# ProProject__STC8H_2024-07-14.net
KiCad netlist of a schematic drawn in EasyEDA Pro
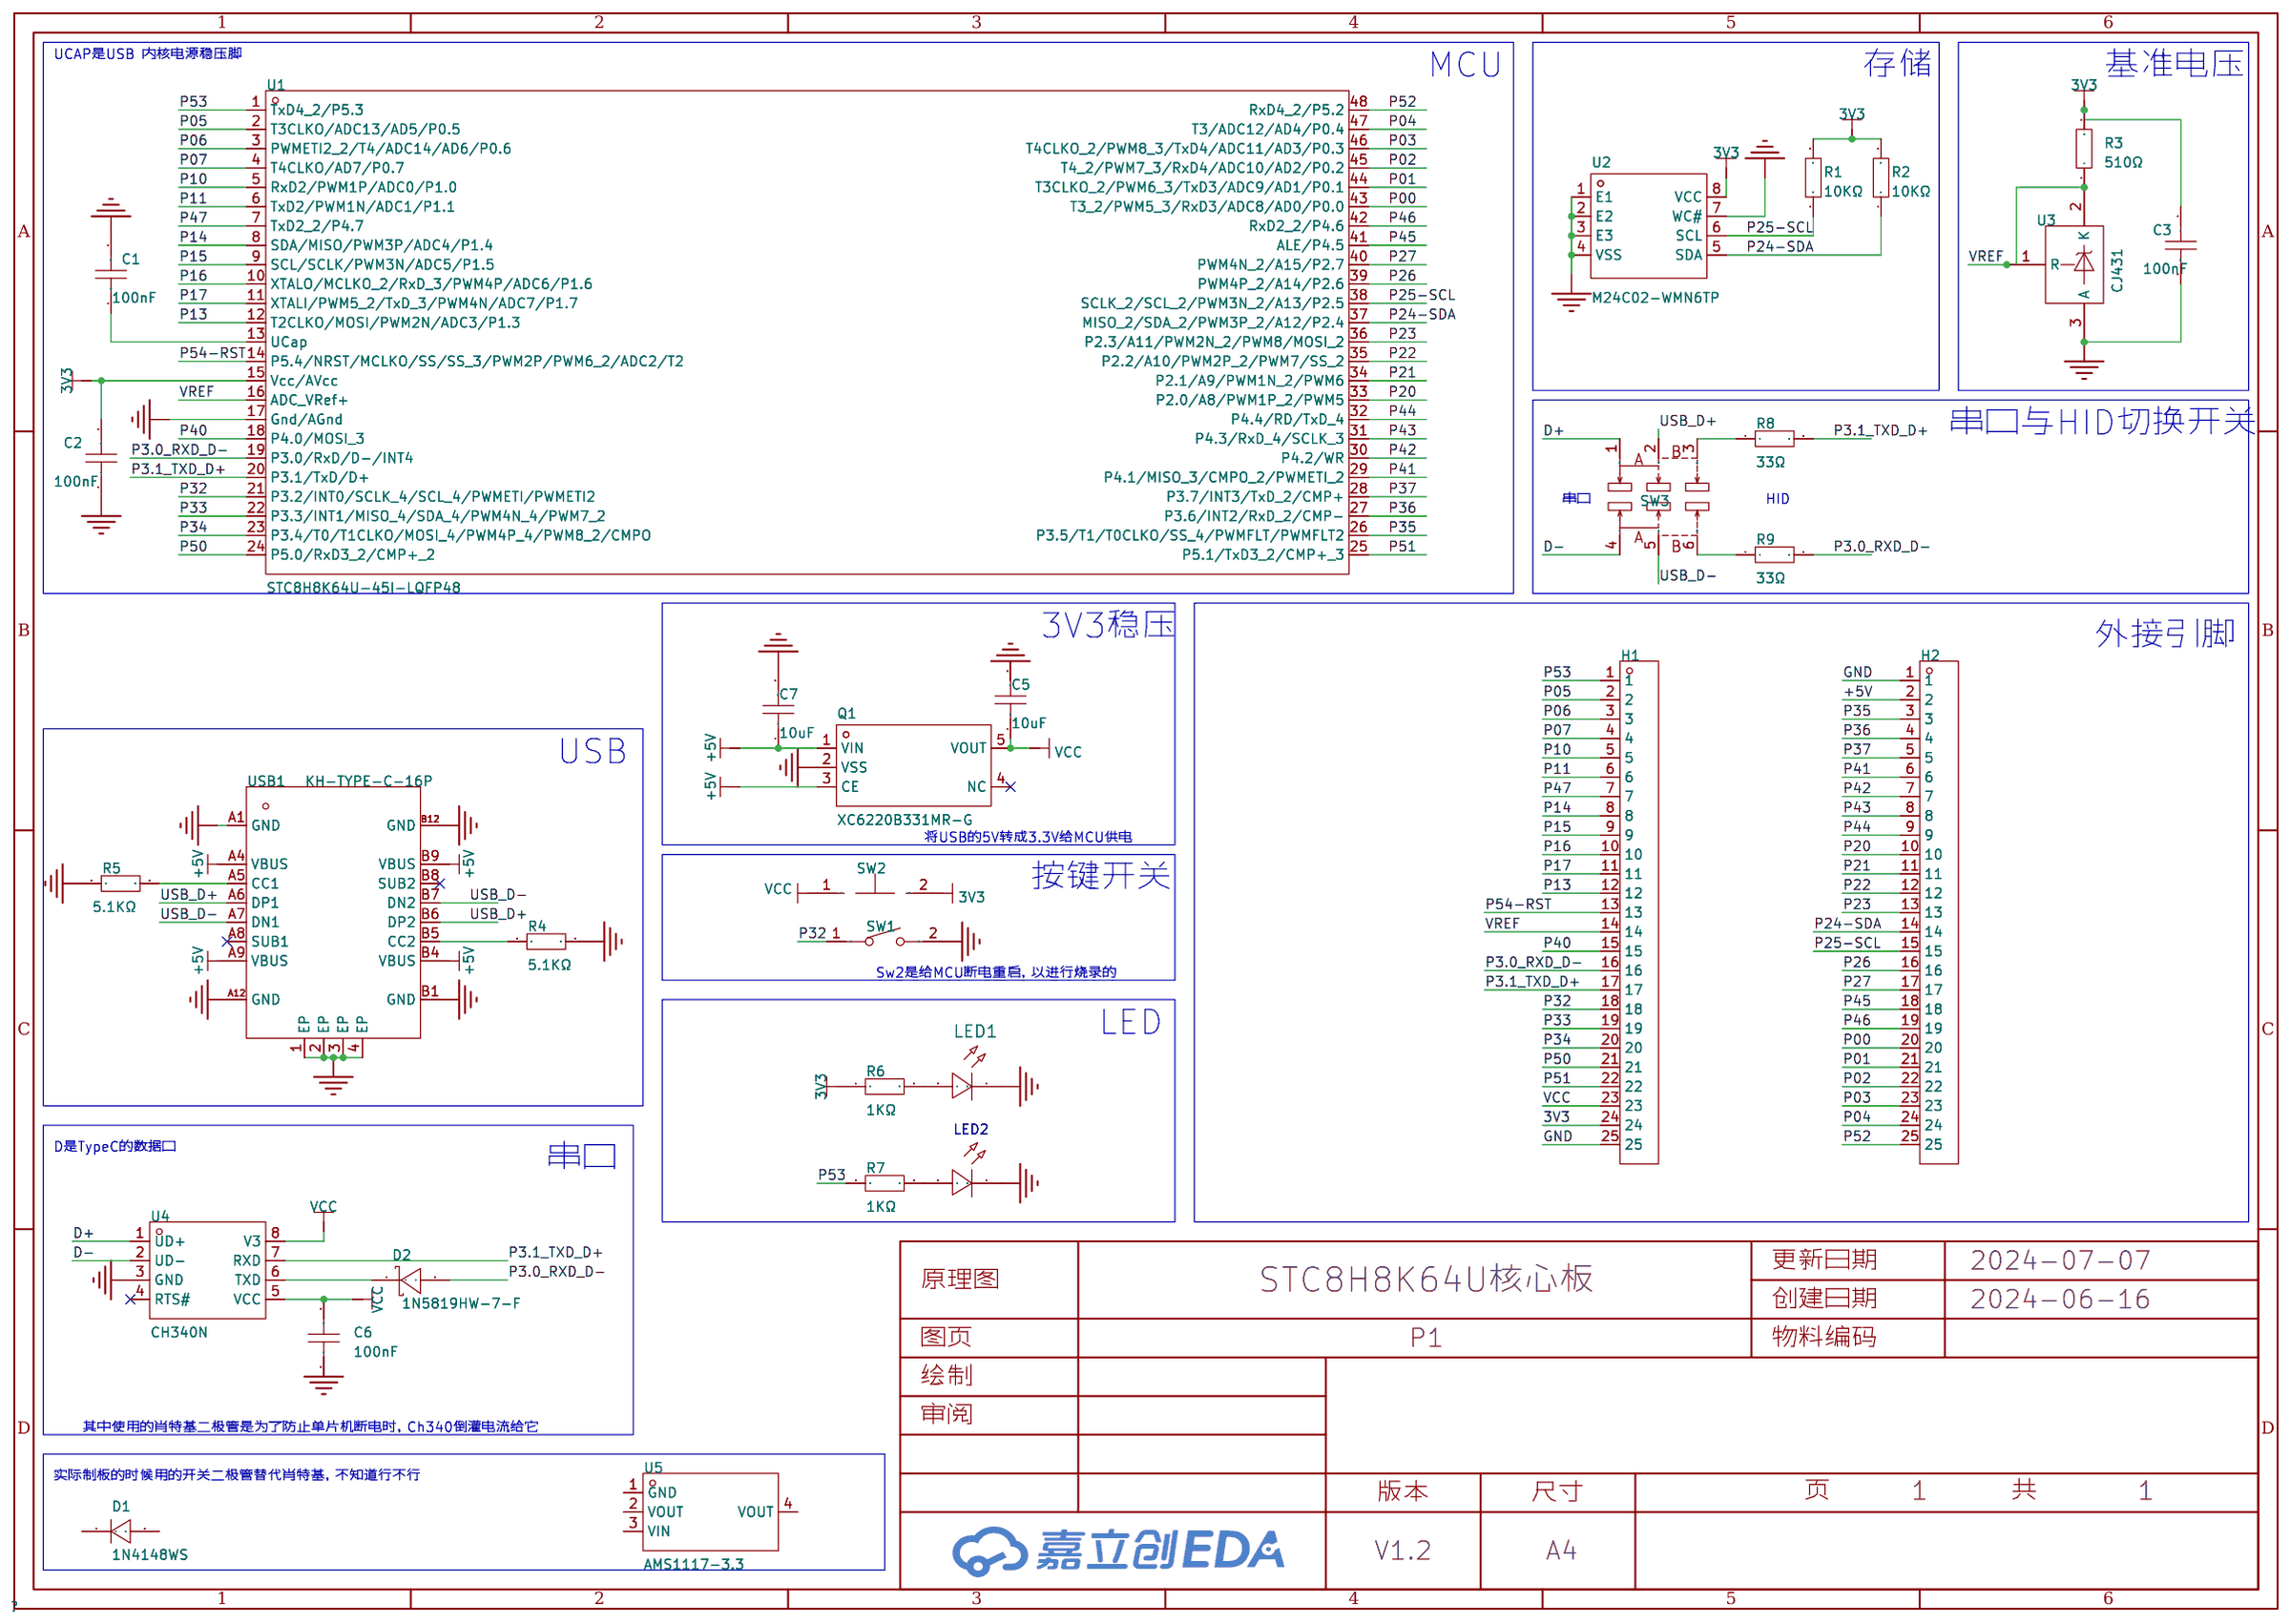
[diagram p0: schematic sheet]

(export (version "E")
  (design (tool "Eeschema 10.0.6"))
  (components
    (comp (ref "C1")
      (value "100nF")
      (footprint "easyedapro:C0603")
      (libsource (lib "easyedapro") (part "CapAcitance"))
    )
    (comp (ref "C2")
      (value "100nF")
      (footprint "easyedapro:C0603")
      (libsource (lib "easyedapro") (part "CapAcitance"))
    )
    (comp (ref "C3")
      (value "100nF")
      (footprint "easyedapro:C0603")
      (libsource (lib "easyedapro") (part "CapAcitance"))
    )
    (comp (ref "C5")
      (value "10uF")
      (footprint "easyedapro:C0603")
      (libsource (lib "easyedapro") (part "CapAcitance"))
    )
    (comp (ref "C6")
      (value "100nF")
      (footprint "easyedapro:C0603")
      (libsource (lib "easyedapro") (part "CapAcitance"))
    )
    (comp (ref "C7")
      (value "10uF")
      (footprint "easyedapro:C0603")
      (libsource (lib "easyedapro") (part "CapAcitance"))
    )
    (comp (ref "D1")
      (value "1N4148WS")
      (footprint "easyedapro:SOD-323_L1.8-W1.3-LS2.5-RD")
      (description "二极管配置:独立式;正向压降(Vf):1.25V@150mA;直流反向耐压(Vr):100V;平均整流电流(Io):150mA;功率:200mW;反向恢复时间(trr):4ns;")
      (fields (field (name "Manufacturer") "CJ(江苏长电/长晶)"))
      (libsource (lib "easyedapro") (part "1N4148WS T4"))
    )
    (comp (ref "D2")
      (value "1N5819HW-7-F")
      (footprint "easyedapro:SOD-123_L2.7-W1.6-LS3.7-RD")
      (description "正向压降(Vf):450mV@1A;直流反向耐压(Vr):40V;平均整流电流(Io):1A;")
      (fields (field (name "Manufacturer") "DIODES(美台)"))
      (libsource (lib "easyedapro") (part "1N5819HW-7-F"))
    )
    (comp (ref "H1")
      (value "X6511WV-25H-C60D30")
      (footprint "easyedapro:HDR-TH_25P-P2.54-V-M")
      (fields (field (name "Manufacturer") "XKB Connection(中国星坤)"))
      (libsource (lib "easyedapro") (part "X6511WV-25H-C30D60"))
    )
    (comp (ref "H2")
      (value "X6511WV-25H-C60D30")
      (footprint "easyedapro:HDR-TH_25P-P2.54-V-M")
      (fields (field (name "Manufacturer") "XKB Connection(中国星坤)"))
      (libsource (lib "easyedapro") (part "X6511WV-25H-C30D60"))
    )
    (comp (ref "LED1")
      (value "~")
      (footprint "easyedapro:LED_0805")
      (libsource (lib "easyedapro") (part "LED_R"))
    )
    (comp (ref "LED2")
      (value "~")
      (footprint "easyedapro:LED_0805")
      (libsource (lib "easyedapro") (part "LED_B"))
    )
    (comp (ref "Q1")
      (value "XC6220B331MR-G")
      (footprint "easyedapro:SOT-25_L3.0-W1.6-P0.95-LS2.8-TL")
      (description "输出类型:固定;最大输入电压:6V;输出电压:3.3V;最大输出电流:1A;电源纹波抑制比(PSRR):50dB@(1kHz);输出极性:正极;")
      (fields (field (name "Manufacturer") "TOREX(特瑞仕)"))
      (libsource (lib "easyedapro") (part "XC6220B331MR-G"))
    )
    (comp (ref "R1") (value "10KΩ") (footprint "easyedapro:R0603") (libsource (lib "easyedapro") (part "电阻")))
    (comp (ref "R2") (value "10KΩ") (footprint "easyedapro:R0603") (libsource (lib "easyedapro") (part "电阻")))
    (comp (ref "R3") (value "510Ω") (footprint "easyedapro:R0603") (libsource (lib "easyedapro") (part "电阻")))
    (comp (ref "R4")
      (value "5.1KΩ")
      (footprint "easyedapro:R0603")
      (libsource (lib "easyedapro") (part "电阻"))
    )
    (comp (ref "R5")
      (value "5.1KΩ")
      (footprint "easyedapro:R0603")
      (libsource (lib "easyedapro") (part "电阻"))
    )
    (comp (ref "R6") (value "1KΩ") (footprint "easyedapro:R0603") (libsource (lib "easyedapro") (part "电阻")))
    (comp (ref "R7") (value "1KΩ") (footprint "easyedapro:R0603") (libsource (lib "easyedapro") (part "电阻")))
    (comp (ref "R8") (value "33Ω") (footprint "easyedapro:R0603") (libsource (lib "easyedapro") (part "电阻")))
    (comp (ref "R9") (value "33Ω") (footprint "easyedapro:R0603") (libsource (lib "easyedapro") (part "电阻")))
    (comp (ref "SW1")
      (value "TS-1088-AR02016")
      (footprint "easyedapro:SW-SMD_L3.9-W3.0-P4.45")
      (fields (field (name "Manufacturer") "XUNPU(讯普)"))
      (libsource (lib "easyedapro") (part "TS-1088-AR02016"))
    )
    (comp (ref "SW2")
      (value "TS-1089A-B3D4")
      (footprint "easyedapro:KEY-SMD_2P-L6.0-W3.8-LS7.30-L")
      (description "电路结构:单刀单掷;按钮形状:圆形按钮;安装方式:-;开关长度:6mm;开关宽度:3.65mm;开关高度:2.6mm;带灯:-;机械寿命:-;")
      (fields (field (name "Manufacturer") "Yuandi(元迪)"))
      (libsource (lib "easyedapro") (part "TS-1089A-B3D4"))
    )
    (comp (ref "SW3")
      (value "MST22D18G2 125")
      (footprint "easyedapro:SW-SMD_MST22D18G2")
      (description "电路结构:双刀双掷;安装方式:立贴;开关颜色:黑色;额定电流(DC):100mA;额定电压(DC):12V;机械寿命:1万次;")
      (fields (field (name "Manufacturer") "SHOU HAN(首韩)"))
      (libsource (lib "easyedapro") (part "MST22D18G2 125"))
    )
    (comp (ref "U1")
      (value "STC8H8K64U-45I-LQFP48")
      (footprint "easyedapro:LQFP-48_L7.0-W7.0-P0.50-LS9.0-BL")
      (description "CPU内核:51系列;程序存储容量:64KB;GPIO端口数量:-;工作电压范围:-;CPU最大主频:-;程序存储器类型:FLASH;")
      (fields (field (name "Manufacturer") "STC(宏晶)"))
      (libsource (lib "easyedapro") (part "STC8H8K64U-45I-LQFP48"))
    )
    (comp (ref "U2")
      (value "M24C02-WMN6TP")
      (footprint "easyedapro:SOIC-8_L4.9-W3.9-P1.27-LS6.0-BL")
      (description "接口类型:I2C;存储容量:2Kbit;")
      (fields (field (name "Manufacturer") "ST(意法半导体)"))
      (libsource (lib "easyedapro") (part "M24C02-WMN6TP"))
    )
    (comp (ref "U3")
      (value "CJ431")
      (footprint "easyedapro:SOT-23-3_L2.9-W1.6-P1.90-LS2.8-BR")
      (description "输出类型:可调;输出电压:2.5V~36V;输出电流:100mA;精度:±0.5%;")
      (fields (field (name "Manufacturer") "CJ(江苏长电/长晶)"))
      (libsource (lib "easyedapro") (part "CJ431_C3113"))
    )
    (comp (ref "U4")
      (value "CH340N")
      (footprint "easyedapro:SOP-8_L4.9-W3.9-P1.27-LS6.0-BL")
      (fields (field (name "Manufacturer") "WCH(南京沁恒)"))
      (libsource (lib "easyedapro") (part "CH340N_C2977777"))
    )
    (comp (ref "U5")
      (value "AMS1117-3.3")
      (footprint "easyedapro:SOT-223-3_L6.5-W3.4-P2.30-LS7.0-BR")
      (description "输出类型:固定;最大输入电压:-;输出电压:3.3V;最大输出电流:1A;电源纹波抑制比(PSRR):72dB@(120Hz);输出极性:正极;")
      (fields (field (name "Manufacturer") "AMS"))
      (libsource (lib "easyedapro") (part "AMS1117-3.3"))
    )
    (comp (ref "USB1")
      (value "KH-TYPE-C-16P")
      (footprint "easyedapro:USB-C-SMD_KH-TYPE-C-16P")
      (description "连接器类型:Type-C;标准:-;公母:母;端口数量:1;触点数量:16P;安装方式:卧贴;额定电流 - 电源:3A;工作温度范围:-40°C~+85°C;")
      (fields (field (name "Manufacturer") "kinghelm(金航标)"))
      (libsource (lib "easyedapro") (part "KH-TYPE-C-16P"))
    )
  )
  (nets
    (net (code "1") (name "+5V") (class "Default")
      (node (ref "C7") (pin "1") (pinfunction "1_1") (pintype "input"))
      (node (ref "H2") (pin "2") (pinfunction "2_2") (pintype "unspecified"))
      (node (ref "Q1") (pin "1") (pinfunction "VIN_1") (pintype "unspecified"))
      (node (ref "Q1") (pin "3") (pinfunction "CE_3") (pintype "unspecified"))
      (node (ref "USB1") (pin "A4") (pinfunction "VBUS_A4") (pintype "unspecified"))
      (node (ref "USB1") (pin "A9") (pinfunction "VBUS_A9") (pintype "unspecified"))
      (node (ref "USB1") (pin "B4") (pinfunction "VBUS_B4") (pintype "unspecified"))
      (node (ref "USB1") (pin "B9") (pinfunction "VBUS_B9") (pintype "unspecified"))
    )
    (net (code "2") (name "/D+") (class "Default")
      (node (ref "SW3") (pin "1") (pinfunction "1_1") (pintype "input"))
      (node (ref "U4") (pin "1") (pinfunction "UD+_1") (pintype "unspecified"))
    )
    (net (code "3") (name "/D-") (class "Default")
      (node (ref "SW3") (pin "4") (pinfunction "4_4") (pintype "input"))
      (node (ref "U4") (pin "2") (pinfunction "UD-_2") (pintype "unspecified"))
    )
    (net (code "4") (name "/P00") (class "Default")
      (node (ref "H2") (pin "20") (pinfunction "20_20") (pintype "unspecified"))
      (node (ref "U1") (pin "43") (pinfunction "T3_2/PWM5_3/RxD3/ADC8/AD0/P0.0_43") (pintype "unspecified"))
    )
    (net (code "5") (name "/P01") (class "Default")
      (node (ref "H2") (pin "21") (pinfunction "21_21") (pintype "unspecified"))
      (node (ref "U1") (pin "44") (pinfunction "T3CLKO_2/PWM6_3/TxD3/ADC9/AD1/P0.1_44") (pintype "unspecified"))
    )
    (net (code "6") (name "/P02") (class "Default")
      (node (ref "H2") (pin "22") (pinfunction "22_22") (pintype "unspecified"))
      (node (ref "U1") (pin "45") (pinfunction "T4_2/PWM7_3/RxD4/ADC10/AD2/P0.2_45") (pintype "unspecified"))
    )
    (net (code "7") (name "/P03") (class "Default")
      (node (ref "H2") (pin "23") (pinfunction "23_23") (pintype "unspecified"))
      (node (ref "U1") (pin "46") (pinfunction "T4CLKO_2/PWM8_3/TxD4/ADC11/AD3/P0.3_46") (pintype "unspecified"))
    )
    (net (code "8") (name "/P3.0_RXD_D-") (class "Default")
      (node (ref "D2") (pin "2") (pinfunction "A_2") (pintype "unspecified"))
      (node (ref "H1") (pin "16") (pinfunction "16_16") (pintype "unspecified"))
      (node (ref "R9") (pin "2") (pinfunction "2_2") (pintype "input"))
      (node (ref "U1") (pin "19") (pinfunction "P3.0/RxD/D-/INT4_19") (pintype "unspecified"))
    )
    (net (code "9") (name "/P3.1_TXD_D+") (class "Default")
      (node (ref "H1") (pin "17") (pinfunction "17_17") (pintype "unspecified"))
      (node (ref "R8") (pin "2") (pinfunction "2_2") (pintype "input"))
      (node (ref "U1") (pin "20") (pinfunction "P3.1/TxD/D+_20") (pintype "unspecified"))
      (node (ref "U4") (pin "7") (pinfunction "RXD_7") (pintype "unspecified"))
    )
    (net (code "10") (name "/P04") (class "Default")
      (node (ref "H2") (pin "24") (pinfunction "24_24") (pintype "unspecified"))
      (node (ref "U1") (pin "47") (pinfunction "T3/ADC12/AD4/P0.4_47") (pintype "unspecified"))
    )
    (net (code "11") (name "/P05") (class "Default")
      (node (ref "H1") (pin "2") (pinfunction "2_2") (pintype "unspecified"))
      (node (ref "U1") (pin "2") (pinfunction "T3CLKO/ADC13/AD5/P0.5_2") (pintype "unspecified"))
    )
    (net (code "12") (name "/P06") (class "Default")
      (node (ref "H1") (pin "3") (pinfunction "3_3") (pintype "unspecified"))
      (node (ref "U1") (pin "3") (pinfunction "PWMETI2_2/T4/ADC14/AD6/P0.6_3") (pintype "unspecified"))
    )
    (net (code "13") (name "/P07") (class "Default")
      (node (ref "H1") (pin "4") (pinfunction "4_4") (pintype "unspecified"))
      (node (ref "U1") (pin "4") (pinfunction "T4CLKO/AD7/P0.7_4") (pintype "unspecified"))
    )
    (net (code "14") (name "/P10") (class "Default")
      (node (ref "H1") (pin "5") (pinfunction "5_5") (pintype "unspecified"))
      (node (ref "U1") (pin "5") (pinfunction "RxD2/PWM1P/ADC0/P1.0_5") (pintype "unspecified"))
    )
    (net (code "15") (name "/P11") (class "Default")
      (node (ref "H1") (pin "6") (pinfunction "6_6") (pintype "unspecified"))
      (node (ref "U1") (pin "6") (pinfunction "TxD2/PWM1N/ADC1/P1.1_6") (pintype "unspecified"))
    )
    (net (code "16") (name "/P13") (class "Default")
      (node (ref "H1") (pin "12") (pinfunction "12_12") (pintype "unspecified"))
      (node (ref "U1") (pin "12") (pinfunction "T2CLKO/MOSI/PWM2N/ADC3/P1.3_12") (pintype "unspecified"))
    )
    (net (code "17") (name "/P14") (class "Default")
      (node (ref "H1") (pin "8") (pinfunction "8_8") (pintype "unspecified"))
      (node (ref "U1") (pin "8") (pinfunction "SDA/MISO/PWM3P/ADC4/P1.4_8") (pintype "unspecified"))
    )
    (net (code "18") (name "/P15") (class "Default")
      (node (ref "H1") (pin "9") (pinfunction "9_9") (pintype "unspecified"))
      (node (ref "U1") (pin "9") (pinfunction "SCL/SCLK/PWM3N/ADC5/P1.5_9") (pintype "unspecified"))
    )
    (net (code "19") (name "/P16") (class "Default")
      (node (ref "H1") (pin "10") (pinfunction "10_10") (pintype "unspecified"))
      (node (ref "U1") (pin "10") (pinfunction "XTALO/MCLKO_2/RxD_3/PWM4P/ADC6/P1.6_10") (pintype "unspecified"))
    )
    (net (code "20") (name "/P17") (class "Default")
      (node (ref "H1") (pin "11") (pinfunction "11_11") (pintype "unspecified"))
      (node (ref "U1") (pin "11") (pinfunction "XTALI/PWM5_2/TxD_3/PWM4N/ADC7/P1.7_11") (pintype "unspecified"))
    )
    (net (code "21") (name "/P20") (class "Default")
      (node (ref "H2") (pin "10") (pinfunction "10_10") (pintype "unspecified"))
      (node (ref "U1") (pin "33") (pinfunction "P2.0/A8/PWM1P_2/PWM5_33") (pintype "unspecified"))
    )
    (net (code "22") (name "/P21") (class "Default")
      (node (ref "H2") (pin "11") (pinfunction "11_11") (pintype "unspecified"))
      (node (ref "U1") (pin "34") (pinfunction "P2.1/A9/PWM1N_2/PWM6_34") (pintype "unspecified"))
    )
    (net (code "23") (name "/P22") (class "Default")
      (node (ref "H2") (pin "12") (pinfunction "12_12") (pintype "unspecified"))
      (node (ref "U1") (pin "35") (pinfunction "P2.2/A10/PWM2P_2/PWM7/SS_2_35") (pintype "unspecified"))
    )
    (net (code "24") (name "/P23") (class "Default")
      (node (ref "H2") (pin "13") (pinfunction "13_13") (pintype "unspecified"))
      (node (ref "U1") (pin "36") (pinfunction "P2.3/A11/PWM2N_2/PWM8/MOSI_2_36") (pintype "unspecified"))
    )
    (net (code "25") (name "/P24-SDA") (class "Default")
      (node (ref "H2") (pin "14") (pinfunction "14_14") (pintype "unspecified"))
      (node (ref "R2") (pin "1") (pinfunction "1_1") (pintype "input"))
      (node (ref "U1") (pin "37") (pinfunction "MISO_2/SDA_2/PWM3P_2/A12/P2.4_37") (pintype "unspecified"))
      (node (ref "U2") (pin "5") (pinfunction "SDA_5") (pintype "unspecified"))
    )
    (net (code "26") (name "/P25-SCL") (class "Default")
      (node (ref "H2") (pin "15") (pinfunction "15_15") (pintype "unspecified"))
      (node (ref "R1") (pin "1") (pinfunction "1_1") (pintype "input"))
      (node (ref "U1") (pin "38") (pinfunction "SCLK_2/SCL_2/PWM3N_2/A13/P2.5_38") (pintype "unspecified"))
      (node (ref "U2") (pin "6") (pinfunction "SCL_6") (pintype "unspecified"))
    )
    (net (code "27") (name "/P26") (class "Default")
      (node (ref "H2") (pin "16") (pinfunction "16_16") (pintype "unspecified"))
      (node (ref "U1") (pin "39") (pinfunction "PWM4P_2/A14/P2.6_39") (pintype "unspecified"))
    )
    (net (code "28") (name "/P27") (class "Default")
      (node (ref "H2") (pin "17") (pinfunction "17_17") (pintype "unspecified"))
      (node (ref "U1") (pin "40") (pinfunction "PWM4N_2/A15/P2.7_40") (pintype "unspecified"))
    )
    (net (code "29") (name "/P32") (class "Default")
      (node (ref "H1") (pin "18") (pinfunction "18_18") (pintype "unspecified"))
      (node (ref "SW1") (pin "1") (pinfunction "1_1") (pintype "unspecified"))
      (node (ref "U1") (pin "21") (pinfunction "P3.2/INT0/SCLK_4/SCL_4/PWMETI/PWMETI2_21") (pintype "unspecified"))
    )
    (net (code "30") (name "/P33") (class "Default")
      (node (ref "H1") (pin "19") (pinfunction "19_19") (pintype "unspecified"))
      (node (ref "U1") (pin "22") (pinfunction "P3.3/INT1/MISO_4/SDA_4/PWM4N_4/PWM7_2_22") (pintype "unspecified"))
    )
    (net (code "31") (name "/P34") (class "Default")
      (node (ref "H1") (pin "20") (pinfunction "20_20") (pintype "unspecified"))
      (node (ref "U1") (pin "23") (pinfunction "P3.4/T0/T1CLKO/MOSI_4/PWM4P_4/PWM8_2/CMPO_23") (pintype "unspecified"))
    )
    (net (code "32") (name "/P35") (class "Default")
      (node (ref "H2") (pin "3") (pinfunction "3_3") (pintype "unspecified"))
      (node (ref "U1") (pin "26") (pinfunction "P3.5/T1/T0CLKO/SS_4/PWMFLT/PWMFLT2_26") (pintype "unspecified"))
    )
    (net (code "33") (name "/P36") (class "Default")
      (node (ref "H2") (pin "4") (pinfunction "4_4") (pintype "unspecified"))
      (node (ref "U1") (pin "27") (pinfunction "P3.6/INT2/RxD_2/CMP-_27") (pintype "unspecified"))
    )
    (net (code "34") (name "/P37") (class "Default")
      (node (ref "H2") (pin "5") (pinfunction "5_5") (pintype "unspecified"))
      (node (ref "U1") (pin "28") (pinfunction "P3.7/INT3/TxD_2/CMP+_28") (pintype "unspecified"))
    )
    (net (code "35") (name "/P40") (class "Default")
      (node (ref "H1") (pin "15") (pinfunction "15_15") (pintype "unspecified"))
      (node (ref "U1") (pin "18") (pinfunction "P4.0/MOSI_3_18") (pintype "unspecified"))
    )
    (net (code "36") (name "/P41") (class "Default")
      (node (ref "H2") (pin "6") (pinfunction "6_6") (pintype "unspecified"))
      (node (ref "U1") (pin "29") (pinfunction "P4.1/MISO_3/CMPO_2/PWMETI_2_29") (pintype "unspecified"))
    )
    (net (code "37") (name "/P42") (class "Default")
      (node (ref "H2") (pin "7") (pinfunction "7_7") (pintype "unspecified"))
      (node (ref "U1") (pin "30") (pinfunction "P4.2/WR_30") (pintype "unspecified"))
    )
    (net (code "38") (name "/P43") (class "Default")
      (node (ref "H2") (pin "8") (pinfunction "8_8") (pintype "unspecified"))
      (node (ref "U1") (pin "31") (pinfunction "P4.3/RxD_4/SCLK_3_31") (pintype "unspecified"))
    )
    (net (code "39") (name "/P44") (class "Default")
      (node (ref "H2") (pin "9") (pinfunction "9_9") (pintype "unspecified"))
      (node (ref "U1") (pin "32") (pinfunction "P4.4/RD/TxD_4_32") (pintype "unspecified"))
    )
    (net (code "40") (name "/P45") (class "Default")
      (node (ref "H2") (pin "18") (pinfunction "18_18") (pintype "unspecified"))
      (node (ref "U1") (pin "41") (pinfunction "ALE/P4.5_41") (pintype "unspecified"))
    )
    (net (code "41") (name "/P46") (class "Default")
      (node (ref "H2") (pin "19") (pinfunction "19_19") (pintype "unspecified"))
      (node (ref "U1") (pin "42") (pinfunction "RxD2_2/P4.6_42") (pintype "unspecified"))
    )
    (net (code "42") (name "/P47") (class "Default")
      (node (ref "H1") (pin "7") (pinfunction "7_7") (pintype "unspecified"))
      (node (ref "U1") (pin "7") (pinfunction "TxD2_2/P4.7_7") (pintype "unspecified"))
    )
    (net (code "43") (name "/P50") (class "Default")
      (node (ref "H1") (pin "21") (pinfunction "21_21") (pintype "unspecified"))
      (node (ref "U1") (pin "24") (pinfunction "P5.0/RxD3_2/CMP+_2_24") (pintype "unspecified"))
    )
    (net (code "44") (name "/P51") (class "Default")
      (node (ref "H1") (pin "22") (pinfunction "22_22") (pintype "unspecified"))
      (node (ref "U1") (pin "25") (pinfunction "P5.1/TxD3_2/CMP+_3_25") (pintype "unspecified"))
    )
    (net (code "45") (name "/P52") (class "Default")
      (node (ref "H2") (pin "25") (pinfunction "25_25") (pintype "unspecified"))
      (node (ref "U1") (pin "48") (pinfunction "RxD4_2/P5.2_48") (pintype "unspecified"))
    )
    (net (code "46") (name "/P53") (class "Default")
      (node (ref "H1") (pin "1") (pinfunction "1_1") (pintype "unspecified"))
      (node (ref "R7") (pin "1") (pinfunction "1_1") (pintype "input"))
      (node (ref "U1") (pin "1") (pinfunction "TxD4_2/P5.3_1") (pintype "unspecified"))
    )
    (net (code "47") (name "/P54-RST") (class "Default")
      (node (ref "H1") (pin "13") (pinfunction "13_13") (pintype "unspecified"))
      (node (ref "U1") (pin "14") (pinfunction "P5.4/NRST/MCLKO/SS/SS_3/PWM2P/PWM6_2/ADC2/T2_14") (pintype "unspecified"))
    )
    (net (code "48") (name "/USB_D+") (class "Default")
      (node (ref "SW3") (pin "2") (pinfunction "2_2") (pintype "input"))
      (node (ref "USB1") (pin "A6") (pinfunction "DP1_A6") (pintype "unspecified"))
      (node (ref "USB1") (pin "B6") (pinfunction "DP2_B6") (pintype "unspecified"))
    )
    (net (code "49") (name "/USB_D-") (class "Default")
      (node (ref "SW3") (pin "5") (pinfunction "5_5") (pintype "input"))
      (node (ref "USB1") (pin "A7") (pinfunction "DN1_A7") (pintype "unspecified"))
      (node (ref "USB1") (pin "B7") (pinfunction "DN2_B7") (pintype "unspecified"))
    )
    (net (code "50") (name "/VREF") (class "Default")
      (node (ref "H1") (pin "14") (pinfunction "14_14") (pintype "unspecified"))
      (node (ref "R3") (pin "1") (pinfunction "1_1") (pintype "input"))
      (node (ref "U1") (pin "16") (pinfunction "ADC_VRef+_16") (pintype "unspecified"))
      (node (ref "U3") (pin "1") (pinfunction "R_1") (pintype "unspecified"))
      (node (ref "U3") (pin "2") (pinfunction "K_2") (pintype "unspecified"))
    )
    (net (code "51") (name "3V3") (class "Default")
      (node (ref "C2") (pin "2") (pinfunction "2_2") (pintype "input"))
      (node (ref "C3") (pin "1") (pinfunction "1_1") (pintype "input"))
      (node (ref "H1") (pin "24") (pinfunction "24_24") (pintype "unspecified"))
      (node (ref "R1") (pin "2") (pinfunction "2_2") (pintype "input"))
      (node (ref "R2") (pin "2") (pinfunction "2_2") (pintype "input"))
      (node (ref "R3") (pin "2") (pinfunction "2_2") (pintype "input"))
      (node (ref "R6") (pin "1") (pinfunction "1_1") (pintype "input"))
      (node (ref "SW2") (pin "2") (pinfunction "2_2") (pintype "input"))
      (node (ref "U1") (pin "15") (pinfunction "Vcc/AVcc_15") (pintype "unspecified"))
      (node (ref "U2") (pin "8") (pinfunction "VCC_8") (pintype "unspecified"))
    )
    (net (code "52") (name "GND") (class "Default")
      (node (ref "C1") (pin "2") (pinfunction "2_2") (pintype "input"))
      (node (ref "C2") (pin "1") (pinfunction "1_1") (pintype "input"))
      (node (ref "C3") (pin "2") (pinfunction "2_2") (pintype "input"))
      (node (ref "C5") (pin "2") (pinfunction "2_2") (pintype "input"))
      (node (ref "C6") (pin "1") (pinfunction "1_1") (pintype "input"))
      (node (ref "C7") (pin "2") (pinfunction "2_2") (pintype "input"))
      (node (ref "H1") (pin "25") (pinfunction "25_25") (pintype "unspecified"))
      (node (ref "H2") (pin "1") (pinfunction "1_1") (pintype "unspecified"))
      (node (ref "LED1") (pin "1") (pinfunction "C_1") (pintype "input"))
      (node (ref "LED2") (pin "1") (pinfunction "C_1") (pintype "input"))
      (node (ref "Q1") (pin "2") (pinfunction "VSS_2") (pintype "unspecified"))
      (node (ref "R4") (pin "2") (pinfunction "2_2") (pintype "input"))
      (node (ref "R5") (pin "1") (pinfunction "1_1") (pintype "input"))
      (node (ref "SW1") (pin "2") (pinfunction "2_2") (pintype "unspecified"))
      (node (ref "U1") (pin "17") (pinfunction "Gnd/AGnd_17") (pintype "unspecified"))
      (node (ref "U2") (pin "1") (pinfunction "E1_1") (pintype "unspecified"))
      (node (ref "U2") (pin "2") (pinfunction "E2_2") (pintype "unspecified"))
      (node (ref "U2") (pin "3") (pinfunction "E3_3") (pintype "unspecified"))
      (node (ref "U2") (pin "4") (pinfunction "VSS_4") (pintype "unspecified"))
      (node (ref "U2") (pin "7") (pinfunction "WC#_7") (pintype "unspecified"))
      (node (ref "U3") (pin "3") (pinfunction "A_3") (pintype "unspecified"))
      (node (ref "U4") (pin "3") (pinfunction "GND_3") (pintype "unspecified"))
      (node (ref "USB1") (pin "1") (pinfunction "EP_1") (pintype "unspecified"))
      (node (ref "USB1") (pin "2") (pinfunction "EP_2") (pintype "unspecified"))
      (node (ref "USB1") (pin "3") (pinfunction "EP_3") (pintype "unspecified"))
      (node (ref "USB1") (pin "4") (pinfunction "EP_4") (pintype "unspecified"))
      (node (ref "USB1") (pin "A1") (pinfunction "GND_A1") (pintype "unspecified"))
      (node (ref "USB1") (pin "A12") (pinfunction "GND_A12") (pintype "unspecified"))
      (node (ref "USB1") (pin "B1") (pinfunction "GND_B1") (pintype "unspecified"))
      (node (ref "USB1") (pin "B12") (pinfunction "GND_B12") (pintype "unspecified"))
    )
    (net (code "53") (name "Net-(D2-K)") (class "Default")
      (node (ref "D2") (pin "1") (pinfunction "K_1") (pintype "unspecified"))
      (node (ref "U4") (pin "6") (pinfunction "TXD_6") (pintype "unspecified"))
    )
    (net (code "54") (name "Net-(LED1-A)") (class "Default")
      (node (ref "LED1") (pin "2") (pinfunction "A_2") (pintype "input"))
      (node (ref "R6") (pin "2") (pinfunction "2_2") (pintype "input"))
    )
    (net (code "55") (name "Net-(LED2-A)") (class "Default")
      (node (ref "LED2") (pin "2") (pinfunction "A_2") (pintype "input"))
      (node (ref "R7") (pin "2") (pinfunction "2_2") (pintype "input"))
    )
    (net (code "56") (name "Net-(R8-Pad1)") (class "Default")
      (node (ref "R8") (pin "1") (pinfunction "1_1") (pintype "input"))
      (node (ref "SW3") (pin "3") (pinfunction "3_3") (pintype "input"))
    )
    (net (code "57") (name "Net-(R9-Pad1)") (class "Default")
      (node (ref "R9") (pin "1") (pinfunction "1_1") (pintype "input"))
      (node (ref "SW3") (pin "6") (pinfunction "6_6") (pintype "input"))
    )
    (net (code "58") (name "Net-(U1-UCap)") (class "Default")
      (node (ref "C1") (pin "1") (pinfunction "1_1") (pintype "input"))
      (node (ref "U1") (pin "13") (pinfunction "UCap_13") (pintype "unspecified"))
    )
    (net (code "59") (name "Net-(USB1-CC1)") (class "Default")
      (node (ref "R5") (pin "2") (pinfunction "2_2") (pintype "input"))
      (node (ref "USB1") (pin "A5") (pinfunction "CC1_A5") (pintype "unspecified"))
    )
    (net (code "60") (name "Net-(USB1-CC2)") (class "Default")
      (node (ref "R4") (pin "1") (pinfunction "1_1") (pintype "input"))
      (node (ref "USB1") (pin "B5") (pinfunction "CC2_B5") (pintype "unspecified"))
    )
    (net (code "61") (name "VCC") (class "Default")
      (node (ref "C5") (pin "1") (pinfunction "1_1") (pintype "input"))
      (node (ref "C6") (pin "2") (pinfunction "2_2") (pintype "input"))
      (node (ref "H1") (pin "23") (pinfunction "23_23") (pintype "unspecified"))
      (node (ref "Q1") (pin "5") (pinfunction "VOUT_5") (pintype "unspecified"))
      (node (ref "SW2") (pin "1") (pinfunction "1_1") (pintype "input"))
      (node (ref "U4") (pin "5") (pinfunction "VCC_5") (pintype "unspecified"))
      (node (ref "U4") (pin "8") (pinfunction "V3_8") (pintype "unspecified"))
    )
    (net (code "62") (name "unconnected-(D1-A-Pad2)") (class "Default")
      (node (ref "D1") (pin "2") (pinfunction "A_2") (pintype "unspecified"))
    )
    (net (code "63") (name "unconnected-(D1-K-Pad1)") (class "Default")
      (node (ref "D1") (pin "1") (pinfunction "K_1") (pintype "unspecified"))
    )
    (net (code "64") (name "unconnected-(Q1-NC-Pad4)") (class "Default")
      (node (ref "Q1") (pin "4") (pinfunction "NC_4") (pintype "unspecified+no_connect"))
    )
    (net (code "65") (name "unconnected-(U4-RTS#-Pad4)") (class "Default")
      (node (ref "U4") (pin "4") (pinfunction "RTS#_4") (pintype "unspecified+no_connect"))
    )
    (net (code "66") (name "unconnected-(U5-GND-Pad1)") (class "Default")
      (node (ref "U5") (pin "1") (pinfunction "GND_1") (pintype "unspecified"))
    )
    (net (code "67") (name "unconnected-(U5-VIN-Pad3)") (class "Default")
      (node (ref "U5") (pin "3") (pinfunction "VIN_3") (pintype "unspecified"))
    )
    (net (code "68") (name "unconnected-(U5-VOUT-Pad2)") (class "Default")
      (node (ref "U5") (pin "2") (pinfunction "VOUT_2") (pintype "unspecified"))
    )
    (net (code "69") (name "unconnected-(U5-VOUT-Pad4)") (class "Default")
      (node (ref "U5") (pin "4") (pinfunction "VOUT_4") (pintype "unspecified"))
    )
    (net (code "70") (name "unconnected-(USB1-SUB1-PadA8)") (class "Default")
      (node (ref "USB1") (pin "A8") (pinfunction "SUB1_A8") (pintype "unspecified+no_connect"))
    )
    (net (code "71") (name "unconnected-(USB1-SUB2-PadB8)") (class "Default")
      (node (ref "USB1") (pin "B8") (pinfunction "SUB2_B8") (pintype "unspecified+no_connect"))
    )
  )
)
